# Supply_DDS.net
KiCad netlist of a schematic drawn in Altium Designer
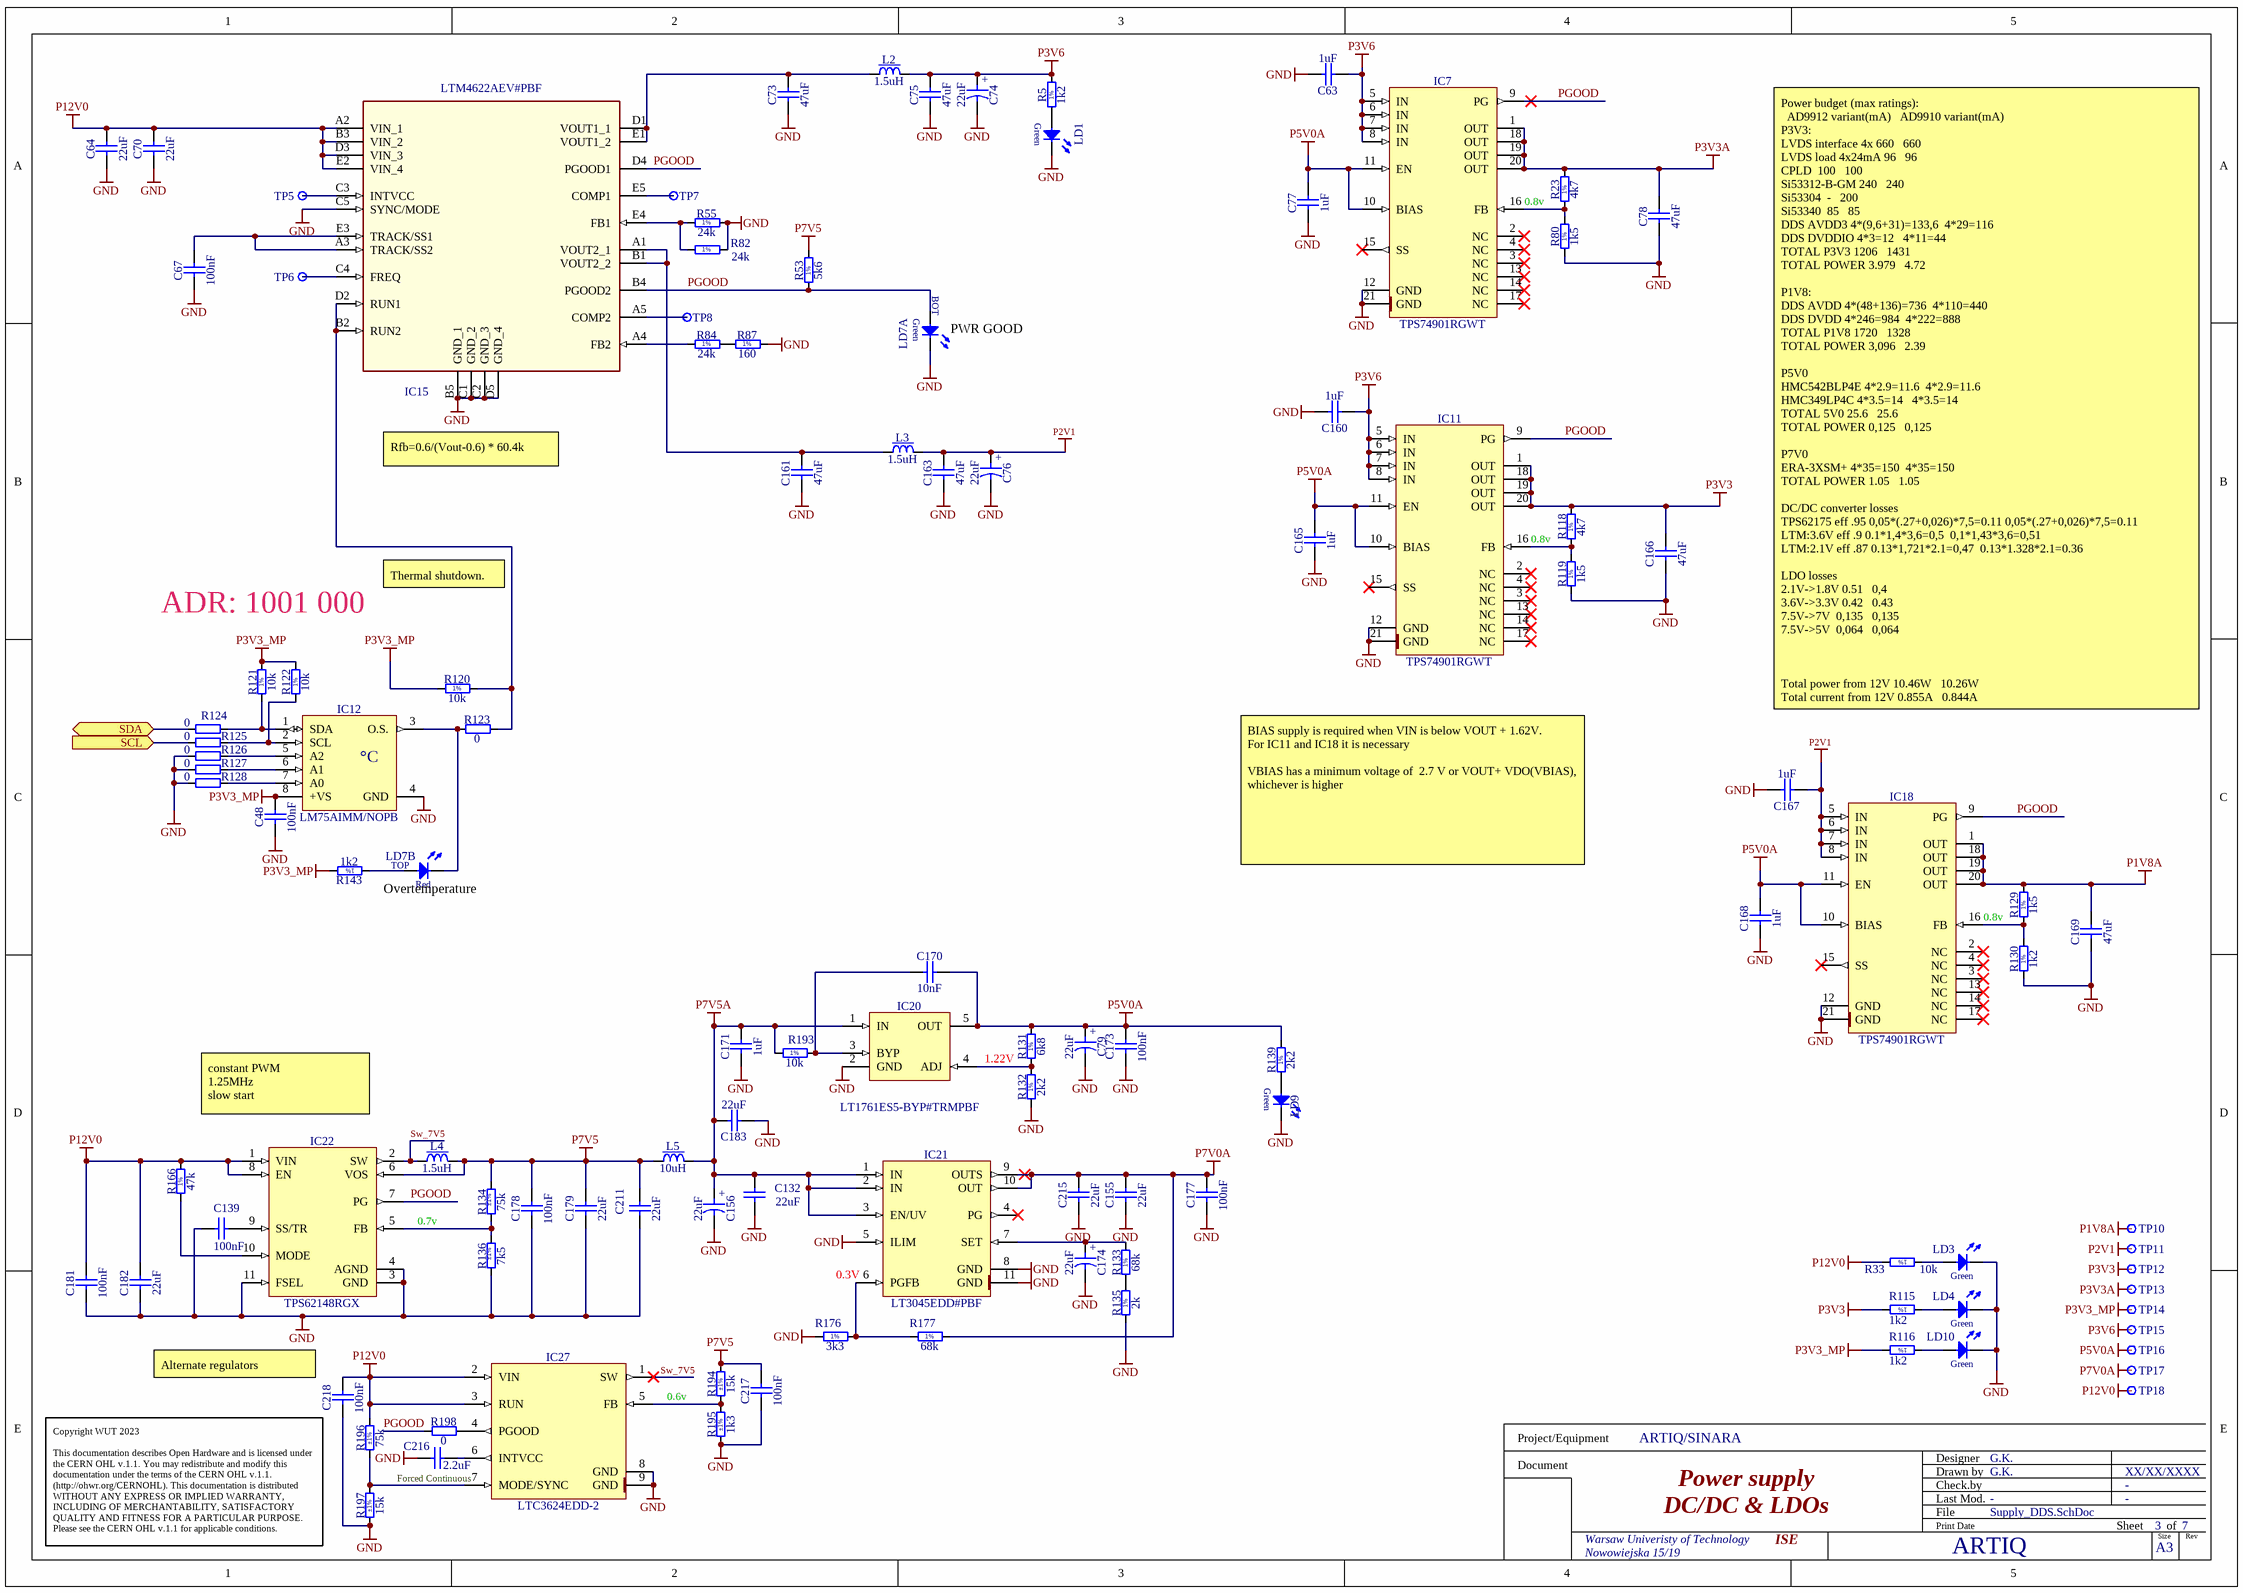
[diagram p0: Supply_DDS.SchDoc]

(export (version "E")
  (design (tool "Eeschema 10.0.6"))
  (components
    (comp (ref "C48")
      (value "100nF")
      (footprint "CAPC1005X55N")
      (description "Non-polarised capacitor")
      (fields
        (field (name "PART NUMBER") "CC0402_100NF_16V_10%_X5R")
        (field (name "VOLTAGE") "16V")
        (field (name "AUTHOR") "CERN DEM JLC")
      )
      (libsource (lib "Capacitors") (part "Capacitor - non polarized"))
    )
    (comp (ref "C63")
      (value "1uF")
      (footprint "CAPC1005X55N")
      (description "Non-polarised capacitor")
      (fields
        (field (name "PART NUMBER") "CC0402_1UF_16V_10%_X5R")
        (field (name "VOLTAGE") "16V")
        (field (name "AUTHOR") "CERN DEM JLC")
      )
      (libsource (lib "Capacitors") (part "Capacitor - non polarized"))
    )
    (comp (ref "C64")
      (value "22uF")
      (footprint "CAPC2012X135N")
      (description "Non-polarised capacitor")
      (fields
        (field (name "PART NUMBER") "CC0805_22UF_16V_10%_X5R")
        (field (name "VOLTAGE") "16V")
        (field (name "AUTHOR") "CERN DEM JLC")
      )
      (libsource (lib "Capacitors") (part "Capacitor - non polarized"))
    )
    (comp (ref "C67")
      (value "100nF")
      (footprint "CAPC1005X55N")
      (description "Non-polarised capacitor")
      (fields
        (field (name "PART NUMBER") "CC0402_100NF_16V_10%_X5R")
        (field (name "VOLTAGE") "16V")
        (field (name "AUTHOR") "CERN DEM JLC")
      )
      (libsource (lib "Capacitors") (part "Capacitor - non polarized"))
    )
    (comp (ref "C70")
      (value "22uF")
      (footprint "CAPC2012X135N")
      (description "Non-polarised capacitor")
      (fields
        (field (name "PART NUMBER") "CC0805_22UF_16V_10%_X5R")
        (field (name "VOLTAGE") "16V")
        (field (name "AUTHOR") "CERN DEM JLC")
      )
      (libsource (lib "Capacitors") (part "Capacitor - non polarized"))
    )
    (comp (ref "C73")
      (value "47uF")
      (footprint "CAPC3225X270N")
      (description "Non-polarised capacitor")
      (fields
        (field (name "PART NUMBER") "CC1210_47UF_10V_20%_X5R")
        (field (name "VOLTAGE") "10V")
        (field (name "AUTHOR") "CERN DEM JLC")
      )
      (libsource (lib "Capacitors") (part "Capacitor - non polarized"))
    )
    (comp (ref "C74")
      (value "22uF")
      (footprint "CAPMP3528X210N")
      (description "Polarised capacitor")
      (fields
        (field (name "PART NUMBER") "CTE3528-21_22UF_10V_10%_LESR0700")
        (field (name "VOLTAGE") "10V")
        (field (name "AUTHOR") "CERN DEM JLC")
      )
      (libsource (lib "Capacitors") (part "Capacitor - polarized"))
    )
    (comp (ref "C75")
      (value "47uF")
      (footprint "CAPC3225X270N")
      (description "Non-polarised capacitor")
      (fields
        (field (name "PART NUMBER") "CC1210_47UF_10V_20%_X5R")
        (field (name "VOLTAGE") "10V")
        (field (name "AUTHOR") "CERN DEM JLC")
      )
      (libsource (lib "Capacitors") (part "Capacitor - non polarized"))
    )
    (comp (ref "C76")
      (value "22uF")
      (footprint "CAPMP3528X210N")
      (description "Polarised capacitor")
      (fields
        (field (name "PART NUMBER") "CTE3528-21_22UF_10V_10%_LESR0700")
        (field (name "VOLTAGE") "10V")
        (field (name "AUTHOR") "CERN DEM JLC")
      )
      (libsource (lib "Capacitors") (part "Capacitor - polarized"))
    )
    (comp (ref "C77")
      (value "1uF")
      (footprint "CAPC1005X55N")
      (description "Non-polarised capacitor")
      (fields
        (field (name "PART NUMBER") "CC0402_1UF_16V_10%_X5R")
        (field (name "VOLTAGE") "16V")
        (field (name "AUTHOR") "CERN DEM JLC")
      )
      (libsource (lib "Capacitors") (part "Capacitor - non polarized"))
    )
    (comp (ref "C78")
      (value "47uF")
      (footprint "CAPC3225X270N")
      (description "Non-polarised capacitor")
      (fields
        (field (name "PART NUMBER") "CC1210_47UF_10V_20%_X5R")
        (field (name "VOLTAGE") "10V")
        (field (name "AUTHOR") "CERN DEM JLC")
      )
      (libsource (lib "Capacitors") (part "Capacitor - non polarized"))
    )
    (comp (ref "C79")
      (value "22uF")
      (footprint "CAPMP3528X210N")
      (description "Polarised capacitor")
      (fields
        (field (name "PART NUMBER") "CTE3528-21_22UF_10V_10%_LESR0700")
        (field (name "VOLTAGE") "10V")
        (field (name "AUTHOR") "CERN DEM JLC")
      )
      (libsource (lib "Capacitors") (part "Capacitor - polarized"))
    )
    (comp (ref "C132")
      (value "22uF")
      (footprint "CAPC2012X135N")
      (description "Non-polarised capacitor")
      (fields
        (field (name "PART NUMBER") "CC0805_22UF_16V_10%_X5R")
        (field (name "VOLTAGE") "16V")
        (field (name "AUTHOR") "CERN DEM JLC")
      )
      (libsource (lib "Capacitors") (part "Capacitor - non polarized"))
    )
    (comp (ref "C139")
      (value "100nF")
      (footprint "CAPC1005X55N")
      (description "Non-polarised capacitor")
      (fields
        (field (name "PART NUMBER") "CC0402_100NF_16V_10%_X5R")
        (field (name "VOLTAGE") "16V")
        (field (name "AUTHOR") "CERN DEM JLC")
      )
      (libsource (lib "Capacitors") (part "Capacitor - non polarized"))
    )
    (comp (ref "C155")
      (value "22uF")
      (footprint "CAPC2012X135N")
      (description "Non-polarised capacitor")
      (fields
        (field (name "PART NUMBER") "CC0805_22UF_16V_10%_X5R")
        (field (name "VOLTAGE") "16V")
        (field (name "AUTHOR") "CERN DEM JLC")
      )
      (libsource (lib "Capacitors") (part "Capacitor - non polarized"))
    )
    (comp (ref "C156")
      (value "22uF")
      (footprint "CAPMP3528X210N")
      (description "Polarised capacitor")
      (fields
        (field (name "PART NUMBER") "CTE3528-21_22UF_10V_10%_LESR0700")
        (field (name "VOLTAGE") "10V")
        (field (name "AUTHOR") "CERN DEM JLC")
      )
      (libsource (lib "Capacitors") (part "Capacitor - polarized"))
    )
    (comp (ref "C160")
      (value "1uF")
      (footprint "CAPC1005X55N")
      (description "Non-polarised capacitor")
      (fields
        (field (name "PART NUMBER") "CC0402_1UF_16V_10%_X5R")
        (field (name "VOLTAGE") "16V")
        (field (name "AUTHOR") "CERN DEM JLC")
      )
      (libsource (lib "Capacitors") (part "Capacitor - non polarized"))
    )
    (comp (ref "C161")
      (value "47uF")
      (footprint "CAPC3225X270N")
      (description "Non-polarised capacitor")
      (fields
        (field (name "PART NUMBER") "CC1210_47UF_10V_20%_X5R")
        (field (name "VOLTAGE") "10V")
        (field (name "AUTHOR") "CERN DEM JLC")
      )
      (libsource (lib "Capacitors") (part "Capacitor - non polarized"))
    )
    (comp (ref "C163")
      (value "47uF")
      (footprint "CAPC3225X270N")
      (description "Non-polarised capacitor")
      (fields
        (field (name "PART NUMBER") "CC1210_47UF_10V_20%_X5R")
        (field (name "VOLTAGE") "10V")
        (field (name "AUTHOR") "CERN DEM JLC")
      )
      (libsource (lib "Capacitors") (part "Capacitor - non polarized"))
    )
    (comp (ref "C165")
      (value "1uF")
      (footprint "CAPC1005X55N")
      (description "Non-polarised capacitor")
      (fields
        (field (name "PART NUMBER") "CC0402_1UF_16V_10%_X5R")
        (field (name "VOLTAGE") "16V")
        (field (name "AUTHOR") "CERN DEM JLC")
      )
      (libsource (lib "Capacitors") (part "Capacitor - non polarized"))
    )
    (comp (ref "C166")
      (value "47uF")
      (footprint "CAPC3225X270N")
      (description "Non-polarised capacitor")
      (fields
        (field (name "PART NUMBER") "CC1210_47UF_10V_20%_X5R")
        (field (name "VOLTAGE") "10V")
        (field (name "AUTHOR") "CERN DEM JLC")
      )
      (libsource (lib "Capacitors") (part "Capacitor - non polarized"))
    )
    (comp (ref "C167")
      (value "1uF")
      (footprint "CAPC1005X55N")
      (description "Non-polarised capacitor")
      (fields
        (field (name "PART NUMBER") "CC0402_1UF_16V_10%_X5R")
        (field (name "VOLTAGE") "16V")
        (field (name "AUTHOR") "CERN DEM JLC")
      )
      (libsource (lib "Capacitors") (part "Capacitor - non polarized"))
    )
    (comp (ref "C168")
      (value "1uF")
      (footprint "CAPC1005X55N")
      (description "Non-polarised capacitor")
      (fields
        (field (name "PART NUMBER") "CC0402_1UF_16V_10%_X5R")
        (field (name "VOLTAGE") "16V")
        (field (name "AUTHOR") "CERN DEM JLC")
      )
      (libsource (lib "Capacitors") (part "Capacitor - non polarized"))
    )
    (comp (ref "C169")
      (value "47uF")
      (footprint "CAPC3225X270N")
      (description "Non-polarised capacitor")
      (fields
        (field (name "PART NUMBER") "CC1210_47UF_10V_20%_X5R")
        (field (name "VOLTAGE") "10V")
        (field (name "AUTHOR") "CERN DEM JLC")
      )
      (libsource (lib "Capacitors") (part "Capacitor - non polarized"))
    )
    (comp (ref "C170")
      (value "10nF")
      (footprint "CAPC1005X55N")
      (description "Non-polarised capacitor")
      (fields
        (field (name "PART NUMBER") "CC0402_10NF_16V_10%_X7R")
        (field (name "VOLTAGE") "16V")
        (field (name "AUTHOR") "CERN DEM JLC")
      )
      (libsource (lib "Capacitors") (part "Capacitor - non polarized"))
    )
    (comp (ref "C171")
      (value "1uF")
      (footprint "CAPC1005X55N")
      (description "Non-polarised capacitor")
      (fields
        (field (name "PART NUMBER") "CC0402_1UF_16V_10%_X5R")
        (field (name "VOLTAGE") "16V")
        (field (name "AUTHOR") "CERN DEM JLC")
      )
      (libsource (lib "Capacitors") (part "Capacitor - non polarized"))
    )
    (comp (ref "C173")
      (value "100nF")
      (footprint "CAPC1005X55N")
      (description "Non-polarised capacitor")
      (fields
        (field (name "PART NUMBER") "CC0402_100NF_16V_10%_X5R")
        (field (name "VOLTAGE") "16V")
        (field (name "AUTHOR") "CERN DEM JLC")
      )
      (libsource (lib "Capacitors") (part "Capacitor - non polarized"))
    )
    (comp (ref "C174")
      (value "22uF")
      (footprint "CAPMP3528X210N")
      (description "Polarised capacitor")
      (fields
        (field (name "PART NUMBER") "CTE3528-21_22UF_10V_10%_LESR0700")
        (field (name "VOLTAGE") "10V")
        (field (name "AUTHOR") "CERN DEM JLC")
      )
      (libsource (lib "Capacitors") (part "Capacitor - polarized"))
    )
    (comp (ref "C177")
      (value "100nF")
      (footprint "CAPC1005X55N")
      (description "Non-polarised capacitor")
      (fields
        (field (name "PART NUMBER") "CC0402_100NF_16V_10%_X5R")
        (field (name "VOLTAGE") "16V")
        (field (name "AUTHOR") "CERN DEM JLC")
      )
      (libsource (lib "Capacitors") (part "Capacitor - non polarized"))
    )
    (comp (ref "C178")
      (value "100nF")
      (footprint "CAPC1005X55N")
      (description "Non-polarised capacitor")
      (fields
        (field (name "PART NUMBER") "CC0402_100NF_16V_10%_X5R")
        (field (name "VOLTAGE") "16V")
        (field (name "AUTHOR") "CERN DEM JLC")
      )
      (libsource (lib "Capacitors") (part "Capacitor - non polarized"))
    )
    (comp (ref "C179")
      (value "22uF")
      (footprint "CAPC2012X135N")
      (description "Non-polarised capacitor")
      (fields
        (field (name "PART NUMBER") "CC0805_22UF_16V_10%_X5R")
        (field (name "VOLTAGE") "16V")
        (field (name "AUTHOR") "CERN DEM JLC")
      )
      (libsource (lib "Capacitors") (part "Capacitor - non polarized"))
    )
    (comp (ref "C181")
      (value "100nF")
      (footprint "CAPC1005X55N")
      (description "Non-polarised capacitor")
      (fields
        (field (name "PART NUMBER") "CC0402_100NF_16V_10%_X5R")
        (field (name "VOLTAGE") "16V")
        (field (name "AUTHOR") "CERN DEM JLC")
      )
      (libsource (lib "Capacitors") (part "Capacitor - non polarized"))
    )
    (comp (ref "C182")
      (value "22uF")
      (footprint "CAPC2012X135N")
      (description "Non-polarised capacitor")
      (fields
        (field (name "PART NUMBER") "CC0805_22UF_16V_10%_X5R")
        (field (name "VOLTAGE") "16V")
        (field (name "AUTHOR") "CERN DEM JLC")
      )
      (libsource (lib "Capacitors") (part "Capacitor - non polarized"))
    )
    (comp (ref "C183")
      (value "22uF")
      (footprint "CAPC2012X135N")
      (description "Non-polarised capacitor")
      (fields
        (field (name "PART NUMBER") "CC0805_22UF_16V_10%_X5R")
        (field (name "VOLTAGE") "16V")
        (field (name "AUTHOR") "CERN DEM JLC")
      )
      (libsource (lib "Capacitors") (part "Capacitor - non polarized"))
    )
    (comp (ref "C211")
      (value "22uF")
      (footprint "CAPC2012X135N")
      (description "Non-polarised capacitor")
      (fields
        (field (name "PART NUMBER") "CC0805_22UF_16V_10%_X5R")
        (field (name "VOLTAGE") "16V")
        (field (name "AUTHOR") "CERN DEM JLC")
      )
      (libsource (lib "Capacitors") (part "Capacitor - non polarized"))
    )
    (comp (ref "C215")
      (value "22uF")
      (footprint "CAPC2012X135N")
      (description "Non-polarised capacitor")
      (fields
        (field (name "PART NUMBER") "CC0805_22UF_16V_10%_X5R")
        (field (name "VOLTAGE") "16V")
        (field (name "AUTHOR") "CERN DEM JLC")
      )
      (libsource (lib "Capacitors") (part "Capacitor - non polarized"))
    )
    (comp (ref "C216")
      (value "2.2uF")
      (footprint "CAPC1005X55N")
      (description "Non-polarised capacitor")
      (fields
        (field (name "PART NUMBER") "CC0402_2.2UF_16V_10%_X5R")
        (field (name "VOLTAGE") "16V")
        (field (name "AUTHOR") "CERN DEM BC")
      )
      (libsource (lib "Capacitors") (part "Capacitor - non polarized"))
    )
    (comp (ref "C217")
      (value "100nF")
      (footprint "CAPC1005X55N")
      (description "Non-polarised capacitor")
      (fields
        (field (name "PART NUMBER") "CC0402_100NF_16V_10%_X5R")
        (field (name "VOLTAGE") "16V")
        (field (name "AUTHOR") "CERN DEM JLC")
      )
      (libsource (lib "Capacitors") (part "Capacitor - non polarized"))
    )
    (comp (ref "C218")
      (value "100nF")
      (footprint "CAPC1005X55N")
      (description "Non-polarised capacitor")
      (fields
        (field (name "PART NUMBER") "CC0402_100NF_16V_10%_X5R")
        (field (name "VOLTAGE") "16V")
        (field (name "AUTHOR") "CERN DEM JLC")
      )
      (libsource (lib "Capacitors") (part "Capacitor - non polarized"))
    )
    (comp (ref "IC7")
      (value "TPS74901RGWT")
      (footprint "QFN65P500X500X100-21N-S325")
      (description "3A, 0.8 to 3.6V Adjustable Low-Dropout Linear Regulator with Programmable Soft-Start")
      (fields (field (name "MANUFACTURER") "TEXAS INSTRUMENTS") (field (name "AUTHOR") "CERN DEM JLC"))
      (libsource (lib "ICs And Semiconductors") (part "TPS74901RGWT"))
    )
    (comp (ref "IC11")
      (value "TPS74901RGWT")
      (footprint "QFN65P500X500X100-21N-S325")
      (description "3A, 0.8 to 3.6V Adjustable Low-Dropout Linear Regulator with Programmable Soft-Start")
      (fields (field (name "MANUFACTURER") "TEXAS INSTRUMENTS") (field (name "AUTHOR") "CERN DEM JLC"))
      (libsource (lib "ICs And Semiconductors") (part "TPS74901RGWT"))
    )
    (comp (ref "IC12")
      (value "LM75AIMM/NOPB")
      (footprint "SOP65P490X109-8N")
      (description "Digital Temperature Sensor and Thermal Watchdog with Two-Wire Interface")
      (fields (field (name "MANUFACTURER") "TEXAS INSTRUMENTS") (field (name "AUTHOR") "CERN DEM JLC"))
      (libsource (lib "ICs And Semiconductors") (part "LM75"))
    )
    (comp (ref "IC15")
      (value "LTM4622AEV#PBF")
      (footprint "LGA25C127P5X5_625X625X190")
      (description "Dual Ultrathin 2A or Single 4A, 3.6V to 20V, 1.5V to 12V   Step-Down DC/DC μModule Regulator")
      (fields (field (name "MANUFACTURER") "LINEAR TECHNOLOGY") (field (name "AUTHOR") "GK"))
      (libsource (lib "LIBRARY_SCH") (part "PM_LTM4622"))
    )
    (comp (ref "IC18")
      (value "TPS74901RGWT")
      (footprint "QFN65P500X500X100-21N-S325")
      (description "3A, 0.8 to 3.6V Adjustable Low-Dropout Linear Regulator with Programmable Soft-Start")
      (fields (field (name "MANUFACTURER") "TEXAS INSTRUMENTS") (field (name "AUTHOR") "CERN DEM JLC"))
      (libsource (lib "ICs And Semiconductors") (part "TPS74901RGWT"))
    )
    (comp (ref "IC20")
      (value "LT1761ES5-BYP#TRMPBF")
      (footprint "SOT95P280X100-5N")
      (description "100mA, Low Noise, LDO Micropower Adjustable Regulator in SOT-23")
      (fields (field (name "MANUFACTURER") "LINEAR TECHNOLOGY") (field (name "AUTHOR") "CERN DEM MR"))
      (libsource (lib "ICs And Semiconductors") (part "LT1761-BYP"))
    )
    (comp (ref "IC21")
      (value "LT3045EDD#PBF")
      (footprint "SON50P300X300X80-11N-R175X248")
      (description "20V, 500mA, Ultralow Noise, Ultrahigh PSRR Linear Regulator")
      (fields (field (name "MANUFACTURER") "LINEAR TECHNOLOGY") (field (name "AUTHOR") "CERN DEM JLC"))
      (libsource (lib "ICs And Semiconductors") (part "LT3045EDD"))
    )
    (comp (ref "IC22")
      (value "TPS62148RGX")
      (footprint "TEXAS_RGX0011A")
      (description "3V-17V 2A Step-Down Converter, High Accuracy, With DCS-Control")
      (fields (field (name "MANUFACTURER") "TEXAS INSTRUMENTS") (field (name "AUTHOR") "CERN DEM MR"))
      (libsource (lib "ICs And Semiconductors") (part "TPS62148"))
    )
    (comp (ref "IC27")
      (value "LTC3624EDD-2")
      (footprint "SON50P300X300X80-9N-R175X248")
      (description "Adjustable, 2A, Synchronous Step-Down Regulator with 3.5µA Quiescent Current")
      (fields (field (name "MANUFACTURER") "LINEAR TECHNOLOGY") (field (name "AUTHOR") "CERN DEM HF"))
      (libsource (lib "ICs And Semiconductors") (part "LTC3624 _DD"))
    )
    (comp (ref "L2")
      (value "1.5uH")
      (footprint "IND_TDK_SPM6530")
      (description "Inductor With Core")
      (fields
        (field (name "PART NUMBER") "IND_1.5UH_20%_TDK_SPM6530")
        (field (name "POWER") "11A")
        (field (name "AUTHOR") "CERN DEM MR")
      )
      (libsource (lib "Inductors & Transformers") (part "Inductor With Magnetic core"))
    )
    (comp (ref "L3")
      (value "1.5uH")
      (footprint "IND_TDK_SPM6530")
      (description "Inductor With Core")
      (fields
        (field (name "PART NUMBER") "IND_1.5UH_20%_TDK_SPM6530")
        (field (name "POWER") "11A")
        (field (name "AUTHOR") "CERN DEM MR")
      )
      (libsource (lib "Inductors & Transformers") (part "Inductor With Magnetic core"))
    )
    (comp (ref "L4")
      (value "1.5uH")
      (footprint "IND_TDK_SPM6530")
      (description "Inductor With Core")
      (fields
        (field (name "PART NUMBER") "IND_1.5UH_20%_TDK_SPM6530")
        (field (name "POWER") "11A")
        (field (name "AUTHOR") "CERN DEM MR")
      )
      (libsource (lib "Inductors & Transformers") (part "Inductor With Magnetic core"))
    )
    (comp (ref "L5")
      (value "10uH")
      (footprint "IND_MURATA-PS_8400")
      (description "Inductor With Core")
      (fields
        (field (name "PART NUMBER") "IND_10UH_10%_MURATA-PS_8400")
        (field (name "POWER") "950mA")
        (field (name "AUTHOR") "CERN DEM JLC")
      )
      (libsource (lib "Inductors & Transformers") (part "Inductor With Magnetic core"))
    )
    (comp (ref "LD1")
      (value "Green")
      (footprint "LED_KINGBRIGHT_KPH-1608CGCKr")
      (description "Green 0603")
      (fields
        (field (name "PART NUMBER") "LED_KINGBRIGHT_KPH-1608CGCK")
        (field (name "MANUFACTURER") "KINGBRIGHT")
        (field (name "AUTHOR") "CERN DEM JLC")
      )
      (libsource (lib "LIBRARY_SCH") (part "LED_0603_Green"))
    )
    (comp (ref "LD3")
      (value "Green")
      (footprint "LED_KINGBRIGHT_KPH-1608CGCKr")
      (description "Green 0603")
      (fields
        (field (name "PART NUMBER") "LED_KINGBRIGHT_KPH-1608CGCK")
        (field (name "MANUFACTURER") "KINGBRIGHT")
        (field (name "AUTHOR") "CERN DEM JLC")
      )
      (libsource (lib "LIBRARY_SCH") (part "LED_0603_Green"))
    )
    (comp (ref "LD4")
      (value "Green")
      (footprint "LED_KINGBRIGHT_KPH-1608CGCKr")
      (description "Green 0603")
      (fields
        (field (name "PART NUMBER") "LED_KINGBRIGHT_KPH-1608CGCK")
        (field (name "MANUFACTURER") "KINGBRIGHT")
        (field (name "AUTHOR") "CERN DEM JLC")
      )
      (libsource (lib "LIBRARY_SCH") (part "LED_0603_Green"))
    )
    (comp (ref "LD7")
      (value "Red/Green")
      (footprint "LED_DIALIGHT_571-0112F")
      (description "2x LED  Botom Green, Top Red")
      (fields
        (field (name "PART NUMBER") "LED_DIALIGHT_571-0112F")
        (field (name "MANUFACTURER") "DIALIGHT")
        (field (name "AUTHOR") "CERN DEM JLC")
      )
      (libsource (lib "ICs And Semiconductors") (part "LED x2 G-1C2A-BOT_R-3C4A-TOP"))
    )
    (comp (ref "LD9")
      (value "Green")
      (footprint "LED_KINGBRIGHT_KPH-1608CGCKr")
      (description "Green 0603")
      (fields
        (field (name "PART NUMBER") "LED_KINGBRIGHT_KPH-1608CGCK")
        (field (name "MANUFACTURER") "KINGBRIGHT")
        (field (name "AUTHOR") "CERN DEM JLC")
      )
      (libsource (lib "LIBRARY_SCH") (part "LED_0603_Green"))
    )
    (comp (ref "LD10")
      (value "Green")
      (footprint "LED_KINGBRIGHT_KPH-1608CGCKr")
      (description "Green 0603")
      (fields
        (field (name "PART NUMBER") "LED_KINGBRIGHT_KPH-1608CGCK")
        (field (name "MANUFACTURER") "KINGBRIGHT")
        (field (name "AUTHOR") "CERN DEM JLC")
      )
      (libsource (lib "LIBRARY_SCH") (part "LED_0603_Green"))
    )
    (comp (ref "R5")
      (value "1k2")
      (footprint "RESC1608X55N")
      (description "Resistor - 1%")
      (fields
        (field (name "PART NUMBER") "R0603_1K2_1%_0.1W_100PPM")
        (field (name "POWER") "0.1W")
        (field (name "AUTHOR") "CERN DEM JLC")
      )
      (libsource (lib "Resistors") (part "Resistor - 1%"))
    )
    (comp (ref "R23")
      (value "4k7")
      (footprint "RESC1608X55N")
      (description "Resistor - 1%")
      (fields
        (field (name "PART NUMBER") "R0603_4K7_1%_0.1W_100PPM")
        (field (name "POWER") "0.1W")
        (field (name "AUTHOR") "CERN DEM JLC")
      )
      (libsource (lib "Resistors") (part "Resistor - 1%"))
    )
    (comp (ref "R33")
      (value "10k")
      (footprint "RESC1005X40N")
      (description "Resistor - 1%")
      (fields
        (field (name "PART NUMBER") "R0402_10K_1%_0.0625W_100PPM")
        (field (name "POWER") "0.0625W")
        (field (name "AUTHOR") "CERN DEM JLC")
      )
      (libsource (lib "Resistors") (part "Resistor - 1%"))
    )
    (comp (ref "R53")
      (value "5k6")
      (footprint "RESC1608X55N")
      (description "Resistor - 1%")
      (fields
        (field (name "PART NUMBER") "R0603_5K6_1%_0.1W_100PPM")
        (field (name "POWER") "0.1W")
        (field (name "AUTHOR") "CERN DEM JLC")
      )
      (libsource (lib "Resistors") (part "Resistor - 1%"))
    )
    (comp (ref "R55")
      (value "24k")
      (footprint "RESC1608X55N")
      (description "Resistor - 1%")
      (fields
        (field (name "PART NUMBER") "R0603_24K_1%_0.1W_100PPM")
        (field (name "POWER") "0.1W")
        (field (name "AUTHOR") "CERN DEM JLC")
      )
      (libsource (lib "Resistors") (part "Resistor - 1%"))
    )
    (comp (ref "R80")
      (value "1k5")
      (footprint "RESC1608X55N")
      (description "Resistor - 1%")
      (fields
        (field (name "PART NUMBER") "R0603_1K5_1%_0.1W_100PPM")
        (field (name "POWER") "0.1W")
        (field (name "AUTHOR") "CERN DEM JLC")
      )
      (libsource (lib "Resistors") (part "Resistor - 1%"))
    )
    (comp (ref "R82")
      (value "24k")
      (footprint "RESC1608X55N")
      (description "Resistor - 1%")
      (fields
        (field (name "PART NUMBER") "R0603_24K_1%_0.1W_100PPM")
        (field (name "POWER") "0.1W")
        (field (name "AUTHOR") "CERN DEM JLC")
      )
      (libsource (lib "Resistors") (part "Resistor - 1%"))
    )
    (comp (ref "R84")
      (value "24k")
      (footprint "RESC1608X55N")
      (description "Resistor - 1%")
      (fields
        (field (name "PART NUMBER") "R0603_24K_1%_0.1W_100PPM")
        (field (name "POWER") "0.1W")
        (field (name "AUTHOR") "CERN DEM JLC")
      )
      (libsource (lib "Resistors") (part "Resistor - 1%"))
    )
    (comp (ref "R87")
      (value "160")
      (footprint "RESC1608X55N")
      (description "Resistor - 1%")
      (fields
        (field (name "PART NUMBER") "R0603_160R_1%_0.1W_100PPM")
        (field (name "POWER") "0.1W")
        (field (name "AUTHOR") "CERN DEM JLC")
      )
      (libsource (lib "Resistors") (part "Resistor - 1%"))
    )
    (comp (ref "R115")
      (value "1k2")
      (footprint "RESC1608X55N")
      (description "Resistor - 1%")
      (fields
        (field (name "PART NUMBER") "R0603_1K2_1%_0.1W_100PPM")
        (field (name "POWER") "0.1W")
        (field (name "AUTHOR") "CERN DEM JLC")
      )
      (libsource (lib "Resistors") (part "Resistor - 1%"))
    )
    (comp (ref "R116")
      (value "1k2")
      (footprint "RESC1608X55N")
      (description "Resistor - 1%")
      (fields
        (field (name "PART NUMBER") "R0603_1K2_1%_0.1W_100PPM")
        (field (name "POWER") "0.1W")
        (field (name "AUTHOR") "CERN DEM JLC")
      )
      (libsource (lib "Resistors") (part "Resistor - 1%"))
    )
    (comp (ref "R118")
      (value "4k7")
      (footprint "RESC1608X55N")
      (description "Resistor - 1%")
      (fields
        (field (name "PART NUMBER") "R0603_4K7_1%_0.1W_100PPM")
        (field (name "POWER") "0.1W")
        (field (name "AUTHOR") "CERN DEM JLC")
      )
      (libsource (lib "Resistors") (part "Resistor - 1%"))
    )
    (comp (ref "R119")
      (value "1k5")
      (footprint "RESC1608X55N")
      (description "Resistor - 1%")
      (fields
        (field (name "PART NUMBER") "R0603_1K5_1%_0.1W_100PPM")
        (field (name "POWER") "0.1W")
        (field (name "AUTHOR") "CERN DEM JLC")
      )
      (libsource (lib "Resistors") (part "Resistor - 1%"))
    )
    (comp (ref "R120")
      (value "10k")
      (footprint "RESC1005X40N")
      (description "Resistor - 1%")
      (fields
        (field (name "PART NUMBER") "R0402_10K_1%_0.0625W_100PPM")
        (field (name "POWER") "0.0625W")
        (field (name "AUTHOR") "CERN DEM JLC")
      )
      (libsource (lib "Resistors") (part "Resistor - 1%"))
    )
    (comp (ref "R121")
      (value "10k")
      (footprint "RESC1005X40N")
      (description "Resistor - 1%")
      (fields
        (field (name "PART NUMBER") "R0402_10K_1%_0.0625W_100PPM")
        (field (name "POWER") "0.0625W")
        (field (name "AUTHOR") "CERN DEM JLC")
      )
      (libsource (lib "Resistors") (part "Resistor - 1%"))
    )
    (comp (ref "R122")
      (value "10k")
      (footprint "RESC1005X40N")
      (description "Resistor - 1%")
      (fields
        (field (name "PART NUMBER") "R0402_10K_1%_0.0625W_100PPM")
        (field (name "POWER") "0.0625W")
        (field (name "AUTHOR") "CERN DEM JLC")
      )
      (libsource (lib "Resistors") (part "Resistor - 1%"))
    )
    (comp (ref "R123")
      (value "0")
      (footprint "RESC1005X40N")
      (description "Resistor")
      (fields
        (field (name "PART NUMBER") "R0402_0R_JUMPER")
        (field (name "MANUFACTURER") "GENERIC")
        (field (name "AUTHOR") "CERN DEM JLC")
      )
      (libsource (lib "Resistors") (part "Resistor"))
    )
    (comp (ref "R124")
      (value "0")
      (footprint "RESC1005X40N")
      (description "Resistor")
      (fields
        (field (name "PART NUMBER") "R0402_0R_JUMPER")
        (field (name "MANUFACTURER") "GENERIC")
        (field (name "AUTHOR") "CERN DEM JLC")
      )
      (libsource (lib "Resistors") (part "Resistor"))
    )
    (comp (ref "R125")
      (value "0")
      (footprint "RESC1005X40N")
      (description "Resistor")
      (fields
        (field (name "PART NUMBER") "R0402_0R_JUMPER")
        (field (name "MANUFACTURER") "GENERIC")
        (field (name "AUTHOR") "CERN DEM JLC")
      )
      (libsource (lib "Resistors") (part "Resistor"))
    )
    (comp (ref "R126")
      (value "0")
      (footprint "RESC1005X40N")
      (description "Resistor")
      (fields
        (field (name "PART NUMBER") "R0402_0R_JUMPER")
        (field (name "MANUFACTURER") "GENERIC")
        (field (name "AUTHOR") "CERN DEM JLC")
      )
      (libsource (lib "Resistors") (part "Resistor"))
    )
    (comp (ref "R127")
      (value "0")
      (footprint "RESC1005X40N")
      (description "Resistor")
      (fields
        (field (name "PART NUMBER") "R0402_0R_JUMPER")
        (field (name "MANUFACTURER") "GENERIC")
        (field (name "AUTHOR") "CERN DEM JLC")
      )
      (libsource (lib "Resistors") (part "Resistor"))
    )
    (comp (ref "R128")
      (value "0")
      (footprint "RESC1005X40N")
      (description "Resistor")
      (fields
        (field (name "PART NUMBER") "R0402_0R_JUMPER")
        (field (name "MANUFACTURER") "GENERIC")
        (field (name "AUTHOR") "CERN DEM JLC")
      )
      (libsource (lib "Resistors") (part "Resistor"))
    )
    (comp (ref "R129")
      (value "1k5")
      (footprint "RESC1608X55N")
      (description "Resistor - 1%")
      (fields
        (field (name "PART NUMBER") "R0603_1K5_1%_0.1W_100PPM")
        (field (name "POWER") "0.1W")
        (field (name "AUTHOR") "CERN DEM JLC")
      )
      (libsource (lib "Resistors") (part "Resistor - 1%"))
    )
    (comp (ref "R130")
      (value "1k2")
      (footprint "RESC1608X55N")
      (description "Resistor - 1%")
      (fields
        (field (name "PART NUMBER") "R0603_1K2_1%_0.1W_100PPM")
        (field (name "POWER") "0.1W")
        (field (name "AUTHOR") "CERN DEM JLC")
      )
      (libsource (lib "Resistors") (part "Resistor - 1%"))
    )
    (comp (ref "R131")
      (value "6k8")
      (footprint "RESC1608X55N")
      (description "Resistor - 1%")
      (fields
        (field (name "PART NUMBER") "R0603_6K8_1%_0.1W_100PPM")
        (field (name "POWER") "0.1W")
        (field (name "AUTHOR") "CERN DEM JLC")
      )
      (libsource (lib "Resistors") (part "Resistor - 1%"))
    )
    (comp (ref "R132")
      (value "2k2")
      (footprint "RESC1608X55N")
      (description "Resistor - 1%")
      (fields
        (field (name "PART NUMBER") "R0603_2K2_1%_0.1W_100PPM")
        (field (name "POWER") "0.1W")
        (field (name "AUTHOR") "CERN DEM JLC")
      )
      (libsource (lib "Resistors") (part "Resistor - 1%"))
    )
    (comp (ref "R133")
      (value "68k")
      (footprint "RESC1005X40N")
      (description "Resistor - 1%")
      (fields
        (field (name "PART NUMBER") "R0402_68K_1%_0.0625W_100PPM")
        (field (name "POWER") "0.0625W")
        (field (name "AUTHOR") "CERN DEM JLC")
      )
      (libsource (lib "Resistors") (part "Resistor - 1%"))
    )
    (comp (ref "R134")
      (value "75k")
      (footprint "RESC1608X55N")
      (description "Resistor - 1%")
      (fields
        (field (name "PART NUMBER") "R0603_75K_1%_0.1W_100PPM")
        (field (name "POWER") "0.1W")
        (field (name "TOLERANCE") "±1%")
        (field (name "AUTHOR") "CERN DEM JLC")
      )
      (libsource (lib "") (part "Resistor - 1%_1"))
    )
    (comp (ref "R135")
      (value "2k")
      (footprint "RESC1005X40N")
      (description "Resistor - 1%")
      (fields
        (field (name "PART NUMBER") "R0402_2K_1%_0.0625W_100PPM")
        (field (name "POWER") "0.0625W")
        (field (name "AUTHOR") "CERN DEM JLC")
      )
      (libsource (lib "Resistors") (part "Resistor - 1%"))
    )
    (comp (ref "R136")
      (value "7k5")
      (footprint "RESC1608X55N")
      (description "Resistor - 1%")
      (fields
        (field (name "PART NUMBER") "R0603_7K5_1%_0.1W_100PPM")
        (field (name "POWER") "0.1W")
        (field (name "TOLERANCE") "±1%")
        (field (name "AUTHOR") "CERN DEM JLC")
      )
      (libsource (lib "") (part "Resistor - 1%_1"))
    )
    (comp (ref "R139")
      (value "2k2")
      (footprint "RESC1608X55N")
      (description "Resistor - 1%")
      (fields
        (field (name "PART NUMBER") "R0603_2K2_1%_0.1W_100PPM")
        (field (name "POWER") "0.1W")
        (field (name "AUTHOR") "CERN DEM JLC")
      )
      (libsource (lib "Resistors") (part "Resistor - 1%"))
    )
    (comp (ref "R143")
      (value "1k2")
      (footprint "RESC1608X55N")
      (description "Resistor - 1%")
      (fields
        (field (name "PART NUMBER") "R0603_1K2_1%_0.1W_100PPM")
        (field (name "POWER") "0.1W")
        (field (name "AUTHOR") "CERN DEM JLC")
      )
      (libsource (lib "Resistors") (part "Resistor - 1%"))
    )
    (comp (ref "R166")
      (value "47k")
      (footprint "RESC1608X55N")
      (description "Resistor - 1%")
      (fields
        (field (name "PART NUMBER") "R0603_47K_1%_0.1W_100PPM")
        (field (name "POWER") "0.1W")
        (field (name "AUTHOR") "CERN DEM JLC")
      )
      (libsource (lib "Resistors") (part "Resistor - 1%"))
    )
    (comp (ref "R176")
      (value "3k3")
      (footprint "RESC1608X55N")
      (description "Resistor - 1%")
      (fields
        (field (name "PART NUMBER") "R0603_3K3_1%_0.1W_100PPM")
        (field (name "POWER") "0.1W")
        (field (name "AUTHOR") "CERN DEM JLC")
      )
      (libsource (lib "Resistors") (part "Resistor - 1%"))
    )
    (comp (ref "R177")
      (value "68k")
      (footprint "RESC1005X40N")
      (description "Resistor - 1%")
      (fields
        (field (name "PART NUMBER") "R0402_68K_1%_0.0625W_100PPM")
        (field (name "POWER") "0.0625W")
        (field (name "AUTHOR") "CERN DEM JLC")
      )
      (libsource (lib "Resistors") (part "Resistor - 1%"))
    )
    (comp (ref "R193")
      (value "10k")
      (footprint "RESC1005X40N")
      (description "Resistor - 1%")
      (fields
        (field (name "PART NUMBER") "R0402_10K_1%_0.0625W_100PPM")
        (field (name "POWER") "0.0625W")
        (field (name "AUTHOR") "CERN DEM JLC")
      )
      (libsource (lib "Resistors") (part "Resistor - 1%"))
    )
    (comp (ref "R194")
      (value "15k")
      (footprint "RESC1005X40N")
      (description "Resistor - 1%")
      (fields
        (field (name "TOLERANCE") "±1%")
        (field (name "PART NUMBER") "R0402_15K_1%_0.0625W_100PPM")
        (field (name "POWER") "0.0625W")
        (field (name "AUTHOR") "CERN DEM JMW")
      )
      (libsource (lib "Resistors") (part "Resistor - 1%"))
    )
    (comp (ref "R195")
      (value "1k3")
      (footprint "RESC1005X40N")
      (description "Resistor - 1%")
      (fields
        (field (name "TOLERANCE") "±1%")
        (field (name "PART NUMBER") "R0402_1K3_1%_0.0625W_100PPM")
        (field (name "POWER") "0.0625W")
        (field (name "AUTHOR") "CERN DEM JLC")
      )
      (libsource (lib "Resistors") (part "Resistor - 1%"))
    )
    (comp (ref "R196")
      (value "75k")
      (footprint "RESC1005X40N")
      (description "Resistor - 1%")
      (fields
        (field (name "TOLERANCE") "±1%")
        (field (name "PART NUMBER") "R0402_75K_1%_0.0625W_100PPM")
        (field (name "POWER") "0.0625W")
        (field (name "AUTHOR") "CERN DEM JLC")
      )
      (libsource (lib "Resistors") (part "Resistor - 1%"))
    )
    (comp (ref "R197")
      (value "15k")
      (footprint "RESC1005X40N")
      (description "Resistor - 1%")
      (fields
        (field (name "TOLERANCE") "±1%")
        (field (name "PART NUMBER") "R0402_15K_1%_0.0625W_100PPM")
        (field (name "POWER") "0.0625W")
        (field (name "AUTHOR") "CERN DEM JMW")
      )
      (libsource (lib "Resistors") (part "Resistor - 1%"))
    )
    (comp (ref "R198")
      (value "0")
      (footprint "RESC1005X40N")
      (description "Resistor")
      (fields
        (field (name "PART NUMBER") "R0402_0R_JUMPER")
        (field (name "MANUFACTURER") "GENERIC")
        (field (name "AUTHOR") "CERN DEM JLC")
      )
      (libsource (lib "Resistors") (part "Resistor"))
    )
    (comp (ref "TP5")
      (value "Test Point")
      (footprint "TPS127")
      (fields (field (name "PART NUMBER") "SMD_PAD_1.27X1.27MM") (field (name "AUTHOR") "CERN DEM JLC"))
      (libsource (lib "Eletro-mechanical") (part "Test Point"))
    )
    (comp (ref "TP6")
      (value "Test Point")
      (footprint "TPS127")
      (fields (field (name "PART NUMBER") "SMD_PAD_1.27X1.27MM") (field (name "AUTHOR") "CERN DEM JLC"))
      (libsource (lib "Eletro-mechanical") (part "Test Point"))
    )
    (comp (ref "TP7")
      (value "Test Point")
      (footprint "TPS127")
      (fields (field (name "PART NUMBER") "SMD_PAD_1.27X1.27MM") (field (name "AUTHOR") "CERN DEM JLC"))
      (libsource (lib "Eletro-mechanical") (part "Test Point"))
    )
    (comp (ref "TP8")
      (value "Test Point")
      (footprint "TPS127")
      (fields (field (name "PART NUMBER") "SMD_PAD_1.27X1.27MM") (field (name "AUTHOR") "CERN DEM JLC"))
      (libsource (lib "Eletro-mechanical") (part "Test Point"))
    )
    (comp (ref "TP10")
      (value "Test Point")
      (footprint "TPS127")
      (fields (field (name "PART NUMBER") "SMD_PAD_1.27X1.27MM") (field (name "AUTHOR") "CERN DEM JLC"))
      (libsource (lib "Eletro-mechanical") (part "Test Point"))
    )
    (comp (ref "TP11")
      (value "Test Point")
      (footprint "TPS127")
      (fields (field (name "PART NUMBER") "SMD_PAD_1.27X1.27MM") (field (name "AUTHOR") "CERN DEM JLC"))
      (libsource (lib "Eletro-mechanical") (part "Test Point"))
    )
    (comp (ref "TP12")
      (value "Test Point")
      (footprint "TPS127")
      (fields (field (name "PART NUMBER") "SMD_PAD_1.27X1.27MM") (field (name "AUTHOR") "CERN DEM JLC"))
      (libsource (lib "Eletro-mechanical") (part "Test Point"))
    )
    (comp (ref "TP13")
      (value "Test Point")
      (footprint "TPS127")
      (fields (field (name "PART NUMBER") "SMD_PAD_1.27X1.27MM") (field (name "AUTHOR") "CERN DEM JLC"))
      (libsource (lib "Eletro-mechanical") (part "Test Point"))
    )
    (comp (ref "TP14")
      (value "Test Point")
      (footprint "TPS127")
      (fields (field (name "PART NUMBER") "SMD_PAD_1.27X1.27MM") (field (name "AUTHOR") "CERN DEM JLC"))
      (libsource (lib "Eletro-mechanical") (part "Test Point"))
    )
    (comp (ref "TP15")
      (value "Test Point")
      (footprint "TPS127")
      (fields (field (name "PART NUMBER") "SMD_PAD_1.27X1.27MM") (field (name "AUTHOR") "CERN DEM JLC"))
      (libsource (lib "Eletro-mechanical") (part "Test Point"))
    )
    (comp (ref "TP16")
      (value "Test Point")
      (footprint "TPS127")
      (fields (field (name "PART NUMBER") "SMD_PAD_1.27X1.27MM") (field (name "AUTHOR") "CERN DEM JLC"))
      (libsource (lib "Eletro-mechanical") (part "Test Point"))
    )
    (comp (ref "TP17")
      (value "Test Point")
      (footprint "TPS127")
      (fields (field (name "PART NUMBER") "SMD_PAD_1.27X1.27MM") (field (name "AUTHOR") "CERN DEM JLC"))
      (libsource (lib "Eletro-mechanical") (part "Test Point"))
    )
    (comp (ref "TP18")
      (value "Test Point")
      (footprint "TPS127")
      (fields (field (name "PART NUMBER") "SMD_PAD_1.27X1.27MM") (field (name "AUTHOR") "CERN DEM JLC"))
      (libsource (lib "Eletro-mechanical") (part "Test Point"))
    )
  )
  (nets
    (net (code "1") (name "/PGOOD") (class "Default")
      (node (ref "IC11") (pin "9") (pinfunction "PG_9") (pintype "output"))
      (node (ref "IC15") (pin "B4") (pinfunction "PGOOD2_B4") (pintype "open_collector"))
      (node (ref "IC15") (pin "D4") (pinfunction "PGOOD1_D4") (pintype "open_collector"))
      (node (ref "IC18") (pin "9") (pinfunction "PG_9") (pintype "output"))
      (node (ref "IC22") (pin "7") (pinfunction "PG_7") (pintype "output"))
      (node (ref "IC7") (pin "9") (pinfunction "PG_9") (pintype "output"))
      (node (ref "LD7") (pin "2") (pinfunction "A_2") (pintype "passive"))
      (node (ref "R198") (pin "1") (pinfunction "1_1") (pintype "passive"))
      (node (ref "R53") (pin "1") (pinfunction "1_1") (pintype "passive"))
    )
    (net (code "2") (name "/SCL") (class "Default")
      (node (ref "R125") (pin "1") (pinfunction "1_1") (pintype "passive"))
    )
    (net (code "3") (name "/SDA") (class "Default")
      (node (ref "R124") (pin "1") (pinfunction "1_1") (pintype "passive"))
    )
    (net (code "4") (name "/Sw_7V5") (class "Default")
      (node (ref "IC22") (pin "2") (pinfunction "SW_2") (pintype "output"))
      (node (ref "IC27") (pin "1") (pinfunction "SW_1") (pintype "output"))
      (node (ref "L4") (pin "1") (pinfunction "1_1") (pintype "passive"))
    )
    (net (code "5") (name "GND") (class "Default")
      (node (ref "C132") (pin "1") (pinfunction "1_1") (pintype "passive"))
      (node (ref "C139") (pin "2") (pinfunction "2_2") (pintype "passive"))
      (node (ref "C155") (pin "1") (pinfunction "1_1") (pintype "passive"))
      (node (ref "C156") (pin "2") (pinfunction "2_2") (pintype "passive"))
      (node (ref "C160") (pin "2") (pinfunction "2_2") (pintype "passive"))
      (node (ref "C161") (pin "1") (pinfunction "1_1") (pintype "passive"))
      (node (ref "C163") (pin "1") (pinfunction "1_1") (pintype "passive"))
      (node (ref "C165") (pin "1") (pinfunction "1_1") (pintype "passive"))
      (node (ref "C166") (pin "1") (pinfunction "1_1") (pintype "passive"))
      (node (ref "C167") (pin "2") (pinfunction "2_2") (pintype "passive"))
      (node (ref "C168") (pin "1") (pinfunction "1_1") (pintype "passive"))
      (node (ref "C169") (pin "1") (pinfunction "1_1") (pintype "passive"))
      (node (ref "C171") (pin "1") (pinfunction "1_1") (pintype "passive"))
      (node (ref "C173") (pin "1") (pinfunction "1_1") (pintype "passive"))
      (node (ref "C174") (pin "2") (pinfunction "2_2") (pintype "passive"))
      (node (ref "C177") (pin "1") (pinfunction "1_1") (pintype "passive"))
      (node (ref "C178") (pin "1") (pinfunction "1_1") (pintype "passive"))
      (node (ref "C179") (pin "1") (pinfunction "1_1") (pintype "passive"))
      (node (ref "C181") (pin "1") (pinfunction "1_1") (pintype "passive"))
      (node (ref "C182") (pin "1") (pinfunction "1_1") (pintype "passive"))
      (node (ref "C183") (pin "1") (pinfunction "1_1") (pintype "passive"))
      (node (ref "C211") (pin "1") (pinfunction "1_1") (pintype "passive"))
      (node (ref "C215") (pin "1") (pinfunction "1_1") (pintype "passive"))
      (node (ref "C216") (pin "1") (pinfunction "1_1") (pintype "passive"))
      (node (ref "C217") (pin "1") (pinfunction "1_1") (pintype "passive"))
      (node (ref "C218") (pin "1") (pinfunction "1_1") (pintype "passive"))
      (node (ref "C48") (pin "1") (pinfunction "1_1") (pintype "passive"))
      (node (ref "C63") (pin "2") (pinfunction "2_2") (pintype "passive"))
      (node (ref "C64") (pin "1") (pinfunction "1_1") (pintype "passive"))
      (node (ref "C67") (pin "1") (pinfunction "1_1") (pintype "passive"))
      (node (ref "C70") (pin "1") (pinfunction "1_1") (pintype "passive"))
      (node (ref "C73") (pin "1") (pinfunction "1_1") (pintype "passive"))
      (node (ref "C74") (pin "2") (pinfunction "2_2") (pintype "passive"))
      (node (ref "C75") (pin "1") (pinfunction "1_1") (pintype "passive"))
      (node (ref "C76") (pin "2") (pinfunction "2_2") (pintype "passive"))
      (node (ref "C77") (pin "1") (pinfunction "1_1") (pintype "passive"))
      (node (ref "C78") (pin "1") (pinfunction "1_1") (pintype "passive"))
      (node (ref "C79") (pin "2") (pinfunction "2_2") (pintype "passive"))
      (node (ref "IC11") (pin "12") (pinfunction "GND_12") (pintype "power_in"))
      (node (ref "IC11") (pin "21") (pinfunction "GND_21") (pintype "power_in"))
      (node (ref "IC12") (pin "4") (pinfunction "GND_4") (pintype "power_in"))
      (node (ref "IC15") (pin "B5") (pinfunction "GND_1_B5") (pintype "power_in"))
      (node (ref "IC15") (pin "C1") (pinfunction "GND_2_C1") (pintype "power_in"))
      (node (ref "IC15") (pin "C2") (pinfunction "GND_3_C2") (pintype "power_in"))
      (node (ref "IC15") (pin "C5") (pinfunction "SYNC/MODE_C5") (pintype "input"))
      (node (ref "IC15") (pin "D5") (pinfunction "GND_4_D5") (pintype "power_in"))
      (node (ref "IC18") (pin "12") (pinfunction "GND_12") (pintype "power_in"))
      (node (ref "IC18") (pin "21") (pinfunction "GND_21") (pintype "power_in"))
      (node (ref "IC20") (pin "2") (pinfunction "GND_2") (pintype "power_in"))
      (node (ref "IC21") (pin "11") (pinfunction "GND_11") (pintype "power_in"))
      (node (ref "IC21") (pin "5") (pinfunction "ILIM_5") (pintype "input"))
      (node (ref "IC21") (pin "8") (pinfunction "GND_8") (pintype "power_in"))
      (node (ref "IC22") (pin "11") (pinfunction "FSEL_11") (pintype "input"))
      (node (ref "IC22") (pin "3") (pinfunction "GND_3") (pintype "power_in"))
      (node (ref "IC22") (pin "4") (pinfunction "AGND_4") (pintype "power_in"))
      (node (ref "IC27") (pin "8") (pinfunction "GND_8") (pintype "power_in"))
      (node (ref "IC27") (pin "9") (pinfunction "GND_9") (pintype "power_in"))
      (node (ref "IC7") (pin "12") (pinfunction "GND_12") (pintype "power_in"))
      (node (ref "IC7") (pin "21") (pinfunction "GND_21") (pintype "power_in"))
      (node (ref "LD1") (pin "1") (pinfunction "C_1") (pintype "passive"))
      (node (ref "LD10") (pin "1") (pinfunction "C_1") (pintype "passive"))
      (node (ref "LD3") (pin "1") (pinfunction "C_1") (pintype "passive"))
      (node (ref "LD4") (pin "1") (pinfunction "C_1") (pintype "passive"))
      (node (ref "LD7") (pin "1") (pinfunction "C_1") (pintype "passive"))
      (node (ref "LD9") (pin "1") (pinfunction "C_1") (pintype "passive"))
      (node (ref "R119") (pin "1") (pinfunction "1_1") (pintype "passive"))
      (node (ref "R126") (pin "1") (pinfunction "1_1") (pintype "passive"))
      (node (ref "R127") (pin "1") (pinfunction "1_1") (pintype "passive"))
      (node (ref "R128") (pin "1") (pinfunction "1_1") (pintype "passive"))
      (node (ref "R130") (pin "1") (pinfunction "1_1") (pintype "passive"))
      (node (ref "R132") (pin "1") (pinfunction "1_1") (pintype "passive"))
      (node (ref "R135") (pin "1") (pinfunction "1_1") (pintype "passive"))
      (node (ref "R136") (pin "1") (pinfunction "1_1") (pintype "passive"))
      (node (ref "R176") (pin "1") (pinfunction "1_1") (pintype "passive"))
      (node (ref "R195") (pin "1") (pinfunction "1_1") (pintype "passive"))
      (node (ref "R197") (pin "1") (pinfunction "1_1") (pintype "passive"))
      (node (ref "R55") (pin "2") (pinfunction "2_2") (pintype "passive"))
      (node (ref "R80") (pin "1") (pinfunction "1_1") (pintype "passive"))
      (node (ref "R82") (pin "2") (pinfunction "2_2") (pintype "passive"))
      (node (ref "R87") (pin "2") (pinfunction "2_2") (pintype "passive"))
    )
    (net (code "6") (name "Net-(IC7-FB)") (class "Default")
      (node (ref "IC7") (pin "16") (pinfunction "FB_16") (pintype "input"))
      (node (ref "R23") (pin "1") (pinfunction "1_1") (pintype "passive"))
      (node (ref "R80") (pin "2") (pinfunction "2_2") (pintype "passive"))
    )
    (net (code "7") (name "Net-(IC11-FB)") (class "Default")
      (node (ref "IC11") (pin "16") (pinfunction "FB_16") (pintype "input"))
      (node (ref "R118") (pin "1") (pinfunction "1_1") (pintype "passive"))
      (node (ref "R119") (pin "2") (pinfunction "2_2") (pintype "passive"))
    )
    (net (code "8") (name "Net-(IC12-A0)") (class "Default")
      (node (ref "IC12") (pin "7") (pinfunction "A0_7") (pintype "input"))
      (node (ref "R128") (pin "2") (pinfunction "2_2") (pintype "passive"))
    )
    (net (code "9") (name "Net-(IC12-A1)") (class "Default")
      (node (ref "IC12") (pin "6") (pinfunction "A1_6") (pintype "input"))
      (node (ref "R127") (pin "2") (pinfunction "2_2") (pintype "passive"))
    )
    (net (code "10") (name "Net-(IC12-A2)") (class "Default")
      (node (ref "IC12") (pin "5") (pinfunction "A2_5") (pintype "input"))
      (node (ref "R126") (pin "2") (pinfunction "2_2") (pintype "passive"))
    )
    (net (code "11") (name "Net-(IC12-O.S.)") (class "Default")
      (node (ref "IC12") (pin "3") (pinfunction "O.S._3") (pintype "output"))
      (node (ref "LD7") (pin "3") (pinfunction "C_3") (pintype "passive"))
      (node (ref "R123") (pin "1") (pinfunction "1_1") (pintype "passive"))
    )
    (net (code "12") (name "Net-(IC12-SCL)") (class "Default")
      (node (ref "IC12") (pin "2") (pinfunction "SCL_2") (pintype "input"))
      (node (ref "R122") (pin "1") (pinfunction "1_1") (pintype "passive"))
      (node (ref "R125") (pin "2") (pinfunction "2_2") (pintype "passive"))
    )
    (net (code "13") (name "Net-(IC12-SDA)") (class "Default")
      (node (ref "IC12") (pin "1") (pinfunction "SDA_1") (pintype "bidirectional"))
      (node (ref "R121") (pin "1") (pinfunction "1_1") (pintype "passive"))
      (node (ref "R124") (pin "2") (pinfunction "2_2") (pintype "passive"))
    )
    (net (code "14") (name "Net-(IC15-COMP1)") (class "Default")
      (node (ref "IC15") (pin "E5") (pinfunction "COMP1_E5") (pintype "passive"))
      (node (ref "TP7") (pin "1") (pinfunction "1_1") (pintype "bidirectional"))
    )
    (net (code "15") (name "Net-(IC15-COMP2)") (class "Default")
      (node (ref "IC15") (pin "A5") (pinfunction "COMP2_A5") (pintype "passive"))
      (node (ref "TP8") (pin "1") (pinfunction "1_1") (pintype "bidirectional"))
    )
    (net (code "16") (name "Net-(IC15-FB1)") (class "Default")
      (node (ref "IC15") (pin "E4") (pinfunction "FB1_E4") (pintype "input"))
      (node (ref "R55") (pin "1") (pinfunction "1_1") (pintype "passive"))
      (node (ref "R82") (pin "1") (pinfunction "1_1") (pintype "passive"))
    )
    (net (code "17") (name "Net-(IC15-FB2)") (class "Default")
      (node (ref "IC15") (pin "A4") (pinfunction "FB2_A4") (pintype "input"))
      (node (ref "R84") (pin "1") (pinfunction "1_1") (pintype "passive"))
    )
    (net (code "18") (name "Net-(IC15-FREQ)") (class "Default")
      (node (ref "IC15") (pin "C4") (pinfunction "FREQ_C4") (pintype "input"))
      (node (ref "TP6") (pin "1") (pinfunction "1_1") (pintype "bidirectional"))
    )
    (net (code "19") (name "Net-(IC15-INTVCC)") (class "Default")
      (node (ref "IC15") (pin "C3") (pinfunction "INTVCC_C3") (pintype "input"))
      (node (ref "TP5") (pin "1") (pinfunction "1_1") (pintype "bidirectional"))
    )
    (net (code "20") (name "Net-(IC15-RUN1)") (class "Default")
      (node (ref "IC15") (pin "B2") (pinfunction "RUN2_B2") (pintype "input"))
      (node (ref "IC15") (pin "D2") (pinfunction "RUN1_D2") (pintype "input"))
      (node (ref "R120") (pin "2") (pinfunction "2_2") (pintype "passive"))
      (node (ref "R123") (pin "2") (pinfunction "2_2") (pintype "passive"))
    )
    (net (code "21") (name "Net-(IC15-TRACK{slash}SS1)") (class "Default")
      (node (ref "C67") (pin "2") (pinfunction "2_2") (pintype "passive"))
      (node (ref "IC15") (pin "A3") (pinfunction "TRACK/SS2_A3") (pintype "input"))
      (node (ref "IC15") (pin "E3") (pinfunction "TRACK/SS1_E3") (pintype "input"))
    )
    (net (code "22") (name "Net-(IC15-VOUT1_1)") (class "Default")
      (node (ref "C73") (pin "2") (pinfunction "2_2") (pintype "passive"))
      (node (ref "IC15") (pin "D1") (pinfunction "VOUT1_1_D1") (pintype "power_in"))
      (node (ref "IC15") (pin "E1") (pinfunction "VOUT1_2_E1") (pintype "power_in"))
      (node (ref "L2") (pin "1") (pinfunction "1_1") (pintype "passive"))
    )
    (net (code "23") (name "Net-(IC15-VOUT2_1)") (class "Default")
      (node (ref "C161") (pin "2") (pinfunction "2_2") (pintype "passive"))
      (node (ref "IC15") (pin "A1") (pinfunction "VOUT2_1_A1") (pintype "power_in"))
      (node (ref "IC15") (pin "B1") (pinfunction "VOUT2_2_B1") (pintype "power_in"))
      (node (ref "L3") (pin "1") (pinfunction "1_1") (pintype "passive"))
    )
    (net (code "24") (name "Net-(IC18-FB)") (class "Default")
      (node (ref "IC18") (pin "16") (pinfunction "FB_16") (pintype "input"))
      (node (ref "R129") (pin "1") (pinfunction "1_1") (pintype "passive"))
      (node (ref "R130") (pin "2") (pinfunction "2_2") (pintype "passive"))
    )
    (net (code "25") (name "Net-(IC20-ADJ)") (class "Default")
      (node (ref "IC20") (pin "4") (pinfunction "ADJ_4") (pintype "input"))
      (node (ref "R131") (pin "1") (pinfunction "1_1") (pintype "passive"))
      (node (ref "R132") (pin "2") (pinfunction "2_2") (pintype "passive"))
    )
    (net (code "26") (name "Net-(IC20-BYP)") (class "Default")
      (node (ref "C170") (pin "1") (pinfunction "1_1") (pintype "passive"))
      (node (ref "IC20") (pin "3") (pinfunction "BYP_3") (pintype "input"))
      (node (ref "R193") (pin "2") (pinfunction "2_2") (pintype "passive"))
    )
    (net (code "27") (name "Net-(IC21-PGFB)") (class "Default")
      (node (ref "IC21") (pin "6") (pinfunction "PGFB_6") (pintype "input"))
      (node (ref "R176") (pin "2") (pinfunction "2_2") (pintype "passive"))
      (node (ref "R177") (pin "1") (pinfunction "1_1") (pintype "passive"))
    )
    (net (code "28") (name "Net-(IC21-SET)") (class "Default")
      (node (ref "C174") (pin "1") (pinfunction "1_1") (pintype "passive"))
      (node (ref "IC21") (pin "7") (pinfunction "SET_7") (pintype "input"))
      (node (ref "R133") (pin "2") (pinfunction "2_2") (pintype "passive"))
    )
    (net (code "29") (name "Net-(IC22-FB)") (class "Default")
      (node (ref "IC22") (pin "5") (pinfunction "FB_5") (pintype "input"))
      (node (ref "R134") (pin "1") (pinfunction "1_1") (pintype "passive"))
      (node (ref "R136") (pin "2") (pinfunction "2_2") (pintype "passive"))
    )
    (net (code "30") (name "Net-(IC22-MODE)") (class "Default")
      (node (ref "IC22") (pin "10") (pinfunction "MODE_10") (pintype "input"))
      (node (ref "R166") (pin "1") (pinfunction "1_1") (pintype "passive"))
    )
    (net (code "31") (name "Net-(IC22-SS{slash}TR)") (class "Default")
      (node (ref "C139") (pin "1") (pinfunction "1_1") (pintype "passive"))
      (node (ref "IC22") (pin "9") (pinfunction "SS/TR_9") (pintype "input"))
    )
    (net (code "32") (name "Net-(IC27-FB)") (class "Default")
      (node (ref "IC27") (pin "5") (pinfunction "FB_5") (pintype "input"))
      (node (ref "R194") (pin "1") (pinfunction "1_1") (pintype "passive"))
      (node (ref "R195") (pin "2") (pinfunction "2_2") (pintype "passive"))
    )
    (net (code "33") (name "Net-(IC27-INTVCC)") (class "Default")
      (node (ref "C216") (pin "2") (pinfunction "2_2") (pintype "passive"))
      (node (ref "IC27") (pin "6") (pinfunction "INTVCC_6") (pintype "output"))
    )
    (net (code "34") (name "Net-(IC27-MODE{slash}SYNC)") (class "Default")
      (node (ref "IC27") (pin "7") (pinfunction "MODE/SYNC_7") (pintype "input"))
      (node (ref "R196") (pin "1") (pinfunction "1_1") (pintype "passive"))
      (node (ref "R197") (pin "2") (pinfunction "2_2") (pintype "passive"))
    )
    (net (code "35") (name "Net-(IC27-PGOOD)") (class "Default")
      (node (ref "IC27") (pin "4") (pinfunction "PGOOD_4") (pintype "output"))
      (node (ref "R198") (pin "2") (pinfunction "2_2") (pintype "passive"))
    )
    (net (code "36") (name "Net-(LD1-A)") (class "Default")
      (node (ref "LD1") (pin "2") (pinfunction "A_2") (pintype "passive"))
      (node (ref "R5") (pin "1") (pinfunction "1_1") (pintype "passive"))
    )
    (net (code "37") (name "Net-(LD3-A)") (class "Default")
      (node (ref "LD3") (pin "2") (pinfunction "A_2") (pintype "passive"))
      (node (ref "R33") (pin "1") (pinfunction "1_1") (pintype "passive"))
    )
    (net (code "38") (name "Net-(LD4-A)") (class "Default")
      (node (ref "LD4") (pin "2") (pinfunction "A_2") (pintype "passive"))
      (node (ref "R115") (pin "1") (pinfunction "1_1") (pintype "passive"))
    )
    (net (code "39") (name "Net-(LD7B-A)") (class "Default")
      (node (ref "LD7") (pin "4") (pinfunction "A_4") (pintype "passive"))
      (node (ref "R143") (pin "1") (pinfunction "1_1") (pintype "passive"))
    )
    (net (code "40") (name "Net-(LD9-A)") (class "Default")
      (node (ref "LD9") (pin "2") (pinfunction "A_2") (pintype "passive"))
      (node (ref "R139") (pin "1") (pinfunction "1_1") (pintype "passive"))
    )
    (net (code "41") (name "Net-(LD10-A)") (class "Default")
      (node (ref "LD10") (pin "2") (pinfunction "A_2") (pintype "passive"))
      (node (ref "R116") (pin "1") (pinfunction "1_1") (pintype "passive"))
    )
    (net (code "42") (name "Net-(R84-Pad2)") (class "Default")
      (node (ref "R84") (pin "2") (pinfunction "2_2") (pintype "passive"))
      (node (ref "R87") (pin "1") (pinfunction "1_1") (pintype "passive"))
    )
    (net (code "43") (name "Net-(R133-Pad1)") (class "Default")
      (node (ref "R133") (pin "1") (pinfunction "1_1") (pintype "passive"))
      (node (ref "R135") (pin "2") (pinfunction "2_2") (pintype "passive"))
    )
    (net (code "44") (name "P1V8A") (class "Default")
      (node (ref "C169") (pin "2") (pinfunction "2_2") (pintype "passive"))
      (node (ref "IC18") (pin "1") (pinfunction "OUT_1") (pintype "power_in"))
      (node (ref "IC18") (pin "18") (pinfunction "OUT_18") (pintype "power_in"))
      (node (ref "IC18") (pin "19") (pinfunction "OUT_19") (pintype "power_in"))
      (node (ref "IC18") (pin "20") (pinfunction "OUT_20") (pintype "power_in"))
      (node (ref "R129") (pin "2") (pinfunction "2_2") (pintype "passive"))
      (node (ref "TP10") (pin "1") (pinfunction "1_1") (pintype "bidirectional"))
    )
    (net (code "45") (name "P2V1") (class "Default")
      (node (ref "C163") (pin "2") (pinfunction "2_2") (pintype "passive"))
      (node (ref "C167") (pin "1") (pinfunction "1_1") (pintype "passive"))
      (node (ref "C76") (pin "1") (pinfunction "1_1") (pintype "passive"))
      (node (ref "IC18") (pin "5") (pinfunction "IN_5") (pintype "input"))
      (node (ref "IC18") (pin "6") (pinfunction "IN_6") (pintype "input"))
      (node (ref "IC18") (pin "7") (pinfunction "IN_7") (pintype "input"))
      (node (ref "IC18") (pin "8") (pinfunction "IN_8") (pintype "input"))
      (node (ref "L3") (pin "2") (pinfunction "2_2") (pintype "passive"))
      (node (ref "TP11") (pin "1") (pinfunction "1_1") (pintype "bidirectional"))
    )
    (net (code "46") (name "P3V3") (class "Default")
      (node (ref "C166") (pin "2") (pinfunction "2_2") (pintype "passive"))
      (node (ref "IC11") (pin "1") (pinfunction "OUT_1") (pintype "power_in"))
      (node (ref "IC11") (pin "18") (pinfunction "OUT_18") (pintype "power_in"))
      (node (ref "IC11") (pin "19") (pinfunction "OUT_19") (pintype "power_in"))
      (node (ref "IC11") (pin "20") (pinfunction "OUT_20") (pintype "power_in"))
      (node (ref "R115") (pin "2") (pinfunction "2_2") (pintype "passive"))
      (node (ref "R118") (pin "2") (pinfunction "2_2") (pintype "passive"))
      (node (ref "TP12") (pin "1") (pinfunction "1_1") (pintype "bidirectional"))
    )
    (net (code "47") (name "P3V3A") (class "Default")
      (node (ref "C78") (pin "2") (pinfunction "2_2") (pintype "passive"))
      (node (ref "IC7") (pin "1") (pinfunction "OUT_1") (pintype "power_in"))
      (node (ref "IC7") (pin "18") (pinfunction "OUT_18") (pintype "power_in"))
      (node (ref "IC7") (pin "19") (pinfunction "OUT_19") (pintype "power_in"))
      (node (ref "IC7") (pin "20") (pinfunction "OUT_20") (pintype "power_in"))
      (node (ref "R23") (pin "2") (pinfunction "2_2") (pintype "passive"))
      (node (ref "TP13") (pin "1") (pinfunction "1_1") (pintype "bidirectional"))
    )
    (net (code "48") (name "P3V3_MP") (class "Default")
      (node (ref "C48") (pin "2") (pinfunction "2_2") (pintype "passive"))
      (node (ref "IC12") (pin "8") (pinfunction "+VS_8") (pintype "power_in"))
      (node (ref "R116") (pin "2") (pinfunction "2_2") (pintype "passive"))
      (node (ref "R120") (pin "1") (pinfunction "1_1") (pintype "passive"))
      (node (ref "R121") (pin "2") (pinfunction "2_2") (pintype "passive"))
      (node (ref "R122") (pin "2") (pinfunction "2_2") (pintype "passive"))
      (node (ref "R143") (pin "2") (pinfunction "2_2") (pintype "passive"))
      (node (ref "TP14") (pin "1") (pinfunction "1_1") (pintype "bidirectional"))
    )
    (net (code "49") (name "P3V6") (class "Default")
      (node (ref "C160") (pin "1") (pinfunction "1_1") (pintype "passive"))
      (node (ref "C63") (pin "1") (pinfunction "1_1") (pintype "passive"))
      (node (ref "C74") (pin "1") (pinfunction "1_1") (pintype "passive"))
      (node (ref "C75") (pin "2") (pinfunction "2_2") (pintype "passive"))
      (node (ref "IC11") (pin "5") (pinfunction "IN_5") (pintype "input"))
      (node (ref "IC11") (pin "6") (pinfunction "IN_6") (pintype "input"))
      (node (ref "IC11") (pin "7") (pinfunction "IN_7") (pintype "input"))
      (node (ref "IC11") (pin "8") (pinfunction "IN_8") (pintype "input"))
      (node (ref "IC7") (pin "5") (pinfunction "IN_5") (pintype "input"))
      (node (ref "IC7") (pin "6") (pinfunction "IN_6") (pintype "input"))
      (node (ref "IC7") (pin "7") (pinfunction "IN_7") (pintype "input"))
      (node (ref "IC7") (pin "8") (pinfunction "IN_8") (pintype "input"))
      (node (ref "L2") (pin "2") (pinfunction "2_2") (pintype "passive"))
      (node (ref "R5") (pin "2") (pinfunction "2_2") (pintype "passive"))
      (node (ref "TP15") (pin "1") (pinfunction "1_1") (pintype "bidirectional"))
    )
    (net (code "50") (name "P5V0A") (class "Default")
      (node (ref "C165") (pin "2") (pinfunction "2_2") (pintype "passive"))
      (node (ref "C168") (pin "2") (pinfunction "2_2") (pintype "passive"))
      (node (ref "C170") (pin "2") (pinfunction "2_2") (pintype "passive"))
      (node (ref "C173") (pin "2") (pinfunction "2_2") (pintype "passive"))
      (node (ref "C77") (pin "2") (pinfunction "2_2") (pintype "passive"))
      (node (ref "C79") (pin "1") (pinfunction "1_1") (pintype "passive"))
      (node (ref "IC11") (pin "10") (pinfunction "BIAS_10") (pintype "input"))
      (node (ref "IC11") (pin "11") (pinfunction "EN_11") (pintype "input"))
      (node (ref "IC18") (pin "10") (pinfunction "BIAS_10") (pintype "input"))
      (node (ref "IC18") (pin "11") (pinfunction "EN_11") (pintype "input"))
      (node (ref "IC20") (pin "5") (pinfunction "OUT_5") (pintype "power_in"))
      (node (ref "IC7") (pin "10") (pinfunction "BIAS_10") (pintype "input"))
      (node (ref "IC7") (pin "11") (pinfunction "EN_11") (pintype "input"))
      (node (ref "R131") (pin "2") (pinfunction "2_2") (pintype "passive"))
      (node (ref "R139") (pin "2") (pinfunction "2_2") (pintype "passive"))
      (node (ref "TP16") (pin "1") (pinfunction "1_1") (pintype "bidirectional"))
    )
    (net (code "51") (name "P7V0A") (class "Default")
      (node (ref "C155") (pin "2") (pinfunction "2_2") (pintype "passive"))
      (node (ref "C177") (pin "2") (pinfunction "2_2") (pintype "passive"))
      (node (ref "C215") (pin "2") (pinfunction "2_2") (pintype "passive"))
      (node (ref "IC21") (pin "10") (pinfunction "OUT_10") (pintype "output"))
      (node (ref "IC21") (pin "9") (pinfunction "OUTS_9") (pintype "output"))
      (node (ref "R177") (pin "2") (pinfunction "2_2") (pintype "passive"))
      (node (ref "TP17") (pin "1") (pinfunction "1_1") (pintype "bidirectional"))
    )
    (net (code "52") (name "P7V5") (class "Default")
      (node (ref "C178") (pin "2") (pinfunction "2_2") (pintype "passive"))
      (node (ref "C179") (pin "2") (pinfunction "2_2") (pintype "passive"))
      (node (ref "C211") (pin "2") (pinfunction "2_2") (pintype "passive"))
      (node (ref "C217") (pin "2") (pinfunction "2_2") (pintype "passive"))
      (node (ref "IC22") (pin "6") (pinfunction "VOS_6") (pintype "input"))
      (node (ref "L4") (pin "2") (pinfunction "2_2") (pintype "passive"))
      (node (ref "L5") (pin "1") (pinfunction "1_1") (pintype "passive"))
      (node (ref "R134") (pin "2") (pinfunction "2_2") (pintype "passive"))
      (node (ref "R194") (pin "2") (pinfunction "2_2") (pintype "passive"))
      (node (ref "R53") (pin "2") (pinfunction "2_2") (pintype "passive"))
    )
    (net (code "53") (name "P7V5A") (class "Default")
      (node (ref "C132") (pin "2") (pinfunction "2_2") (pintype "passive"))
      (node (ref "C156") (pin "1") (pinfunction "1_1") (pintype "passive"))
      (node (ref "C171") (pin "2") (pinfunction "2_2") (pintype "passive"))
      (node (ref "C183") (pin "2") (pinfunction "2_2") (pintype "passive"))
      (node (ref "IC20") (pin "1") (pinfunction "IN_1") (pintype "input"))
      (node (ref "IC21") (pin "1") (pinfunction "IN_1") (pintype "input"))
      (node (ref "IC21") (pin "2") (pinfunction "IN_2") (pintype "input"))
      (node (ref "IC21") (pin "3") (pinfunction "EN/UV_3") (pintype "input"))
      (node (ref "L5") (pin "2") (pinfunction "2_2") (pintype "passive"))
      (node (ref "R193") (pin "1") (pinfunction "1_1") (pintype "passive"))
    )
    (net (code "54") (name "P12V0") (class "Default")
      (node (ref "C181") (pin "2") (pinfunction "2_2") (pintype "passive"))
      (node (ref "C182") (pin "2") (pinfunction "2_2") (pintype "passive"))
      (node (ref "C218") (pin "2") (pinfunction "2_2") (pintype "passive"))
      (node (ref "C64") (pin "2") (pinfunction "2_2") (pintype "passive"))
      (node (ref "C70") (pin "2") (pinfunction "2_2") (pintype "passive"))
      (node (ref "IC15") (pin "A2") (pinfunction "VIN_1_A2") (pintype "power_in"))
      (node (ref "IC15") (pin "B3") (pinfunction "VIN_2_B3") (pintype "power_in"))
      (node (ref "IC15") (pin "D3") (pinfunction "VIN_3_D3") (pintype "power_in"))
      (node (ref "IC15") (pin "E2") (pinfunction "VIN_4_E2") (pintype "power_in"))
      (node (ref "IC22") (pin "1") (pinfunction "VIN_1") (pintype "input"))
      (node (ref "IC22") (pin "8") (pinfunction "EN_8") (pintype "input"))
      (node (ref "IC27") (pin "2") (pinfunction "VIN_2") (pintype "input"))
      (node (ref "IC27") (pin "3") (pinfunction "RUN_3") (pintype "input"))
      (node (ref "R166") (pin "2") (pinfunction "2_2") (pintype "passive"))
      (node (ref "R196") (pin "2") (pinfunction "2_2") (pintype "passive"))
      (node (ref "R33") (pin "2") (pinfunction "2_2") (pintype "passive"))
      (node (ref "TP18") (pin "1") (pinfunction "1_1") (pintype "bidirectional"))
    )
    (net (code "55") (name "unconnected-(IC7-NC-Pad2)") (class "Default")
      (node (ref "IC7") (pin "2") (pinfunction "NC_2") (pintype "passive+no_connect"))
    )
    (net (code "56") (name "unconnected-(IC7-NC-Pad3)") (class "Default")
      (node (ref "IC7") (pin "3") (pinfunction "NC_3") (pintype "passive+no_connect"))
    )
    (net (code "57") (name "unconnected-(IC7-NC-Pad4)") (class "Default")
      (node (ref "IC7") (pin "4") (pinfunction "NC_4") (pintype "passive+no_connect"))
    )
    (net (code "58") (name "unconnected-(IC7-NC-Pad13)") (class "Default")
      (node (ref "IC7") (pin "13") (pinfunction "NC_13") (pintype "passive+no_connect"))
    )
    (net (code "59") (name "unconnected-(IC7-NC-Pad14)") (class "Default")
      (node (ref "IC7") (pin "14") (pinfunction "NC_14") (pintype "passive+no_connect"))
    )
    (net (code "60") (name "unconnected-(IC7-NC-Pad17)") (class "Default")
      (node (ref "IC7") (pin "17") (pinfunction "NC_17") (pintype "passive+no_connect"))
    )
    (net (code "61") (name "unconnected-(IC7-SS-Pad15)") (class "Default")
      (node (ref "IC7") (pin "15") (pinfunction "SS_15") (pintype "output+no_connect"))
    )
    (net (code "62") (name "unconnected-(IC11-NC-Pad2)") (class "Default")
      (node (ref "IC11") (pin "2") (pinfunction "NC_2") (pintype "passive+no_connect"))
    )
    (net (code "63") (name "unconnected-(IC11-NC-Pad3)") (class "Default")
      (node (ref "IC11") (pin "3") (pinfunction "NC_3") (pintype "passive+no_connect"))
    )
    (net (code "64") (name "unconnected-(IC11-NC-Pad4)") (class "Default")
      (node (ref "IC11") (pin "4") (pinfunction "NC_4") (pintype "passive+no_connect"))
    )
    (net (code "65") (name "unconnected-(IC11-NC-Pad13)") (class "Default")
      (node (ref "IC11") (pin "13") (pinfunction "NC_13") (pintype "passive+no_connect"))
    )
    (net (code "66") (name "unconnected-(IC11-NC-Pad14)") (class "Default")
      (node (ref "IC11") (pin "14") (pinfunction "NC_14") (pintype "passive+no_connect"))
    )
    (net (code "67") (name "unconnected-(IC11-NC-Pad17)") (class "Default")
      (node (ref "IC11") (pin "17") (pinfunction "NC_17") (pintype "passive+no_connect"))
    )
    (net (code "68") (name "unconnected-(IC11-SS-Pad15)") (class "Default")
      (node (ref "IC11") (pin "15") (pinfunction "SS_15") (pintype "output+no_connect"))
    )
    (net (code "69") (name "unconnected-(IC18-NC-Pad2)") (class "Default")
      (node (ref "IC18") (pin "2") (pinfunction "NC_2") (pintype "passive+no_connect"))
    )
    (net (code "70") (name "unconnected-(IC18-NC-Pad3)") (class "Default")
      (node (ref "IC18") (pin "3") (pinfunction "NC_3") (pintype "passive+no_connect"))
    )
    (net (code "71") (name "unconnected-(IC18-NC-Pad4)") (class "Default")
      (node (ref "IC18") (pin "4") (pinfunction "NC_4") (pintype "passive+no_connect"))
    )
    (net (code "72") (name "unconnected-(IC18-NC-Pad13)") (class "Default")
      (node (ref "IC18") (pin "13") (pinfunction "NC_13") (pintype "passive+no_connect"))
    )
    (net (code "73") (name "unconnected-(IC18-NC-Pad14)") (class "Default")
      (node (ref "IC18") (pin "14") (pinfunction "NC_14") (pintype "passive+no_connect"))
    )
    (net (code "74") (name "unconnected-(IC18-NC-Pad17)") (class "Default")
      (node (ref "IC18") (pin "17") (pinfunction "NC_17") (pintype "passive+no_connect"))
    )
    (net (code "75") (name "unconnected-(IC18-SS-Pad15)") (class "Default")
      (node (ref "IC18") (pin "15") (pinfunction "SS_15") (pintype "output+no_connect"))
    )
    (net (code "76") (name "unconnected-(IC21-PG-Pad4)") (class "Default")
      (node (ref "IC21") (pin "4") (pinfunction "PG_4") (pintype "output+no_connect"))
    )
  )
)
